# PCB-FirstFloor.net
KiCad netlist of a schematic drawn in Altium Designer
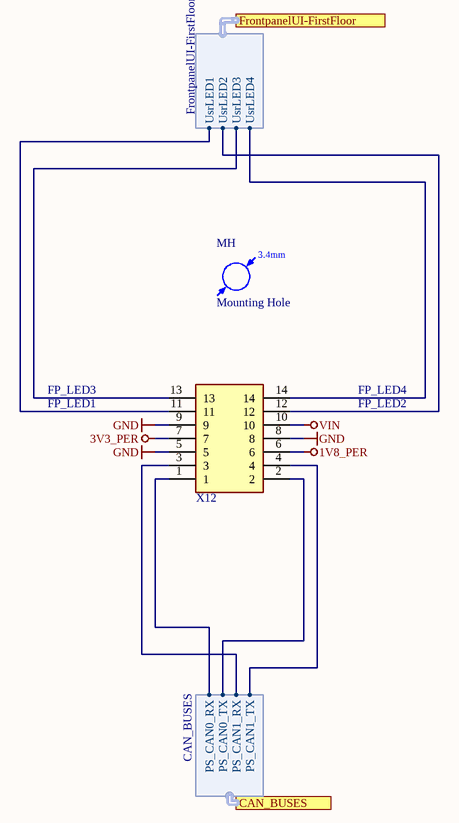
[diagram p0: PCB-FirstFloor.SchDoc]

(export (version "E")
  (design (tool "Eeschema 10.0.6"))
  (components
    (comp (ref "MH")
      (value "Mounting Hole")
      (footprint "MH_3.4")
      (fields (field (name "CREATED FROM") "MHlatky"))
      (libsource (lib "user") (part "Mounting Hole"))
    )
    (comp (ref "X12")
      (value "~")
      (footprint "TE_215309-7")
      (description "[low-cost] Headers & Wire Housings REC ASSY 2X7P VERT [NB: \"2.54-2*7P\" is not a unique MPN]")
      (fields
        (field (name "MANUFACTURER PART NUMBER") "2.54-2*7P")
        (field (name "MANUFACTURER") "Boom Precision Elec")
        (field (name "CREATED FROM") "FRosner/MGeier")
      )
      (libsource (lib "user") (part "215307-7"))
    )
  )
  (nets
    (net (code "3") (name "/PS_CAN0_RX") (class "Default")
      (node (ref "X12") (pin "1") (pinfunction "1_1") (pintype "passive"))
    )
    (net (code "4") (name "/PS_CAN0_TX") (class "Default")
      (node (ref "X12") (pin "2") (pinfunction "2_2") (pintype "passive"))
    )
    (net (code "5") (name "/PS_CAN1_RX") (class "Default")
      (node (ref "X12") (pin "3") (pinfunction "3_3") (pintype "passive"))
    )
    (net (code "6") (name "/PS_CAN1_TX") (class "Default")
      (node (ref "X12") (pin "4") (pinfunction "4_4") (pintype "passive"))
    )
    (net (code "7") (name "/UsrLED1") (class "Default")
      (node (ref "X12") (pin "11") (pinfunction "11_11") (pintype "passive"))
    )
    (net (code "8") (name "/UsrLED2") (class "Default")
      (node (ref "X12") (pin "12") (pinfunction "12_12") (pintype "passive"))
    )
    (net (code "9") (name "/UsrLED3") (class "Default")
      (node (ref "X12") (pin "13") (pinfunction "13_13") (pintype "passive"))
    )
    (net (code "10") (name "/UsrLED4") (class "Default")
      (node (ref "X12") (pin "14") (pinfunction "14_14") (pintype "passive"))
    )
    (net (code "13") (name "1V8_PER") (class "Default")
      (node (ref "X12") (pin "6") (pinfunction "6_6") (pintype "passive"))
    )
    (net (code "14") (name "3V3_PER") (class "Default")
      (node (ref "X12") (pin "7") (pinfunction "7_7") (pintype "passive"))
    )
    (net (code "15") (name "GND") (class "Default")
      (node (ref "X12") (pin "5") (pinfunction "5_5") (pintype "passive"))
      (node (ref "X12") (pin "8") (pinfunction "8_8") (pintype "passive"))
      (node (ref "X12") (pin "9") (pinfunction "9_9") (pintype "passive"))
    )
    (net (code "16") (name "VIN") (class "Default")
      (node (ref "X12") (pin "10") (pinfunction "10_10") (pintype "passive"))
    )
  )
)
